# GeigerCounter.net
KiCad netlist of a schematic drawn in EAGLE
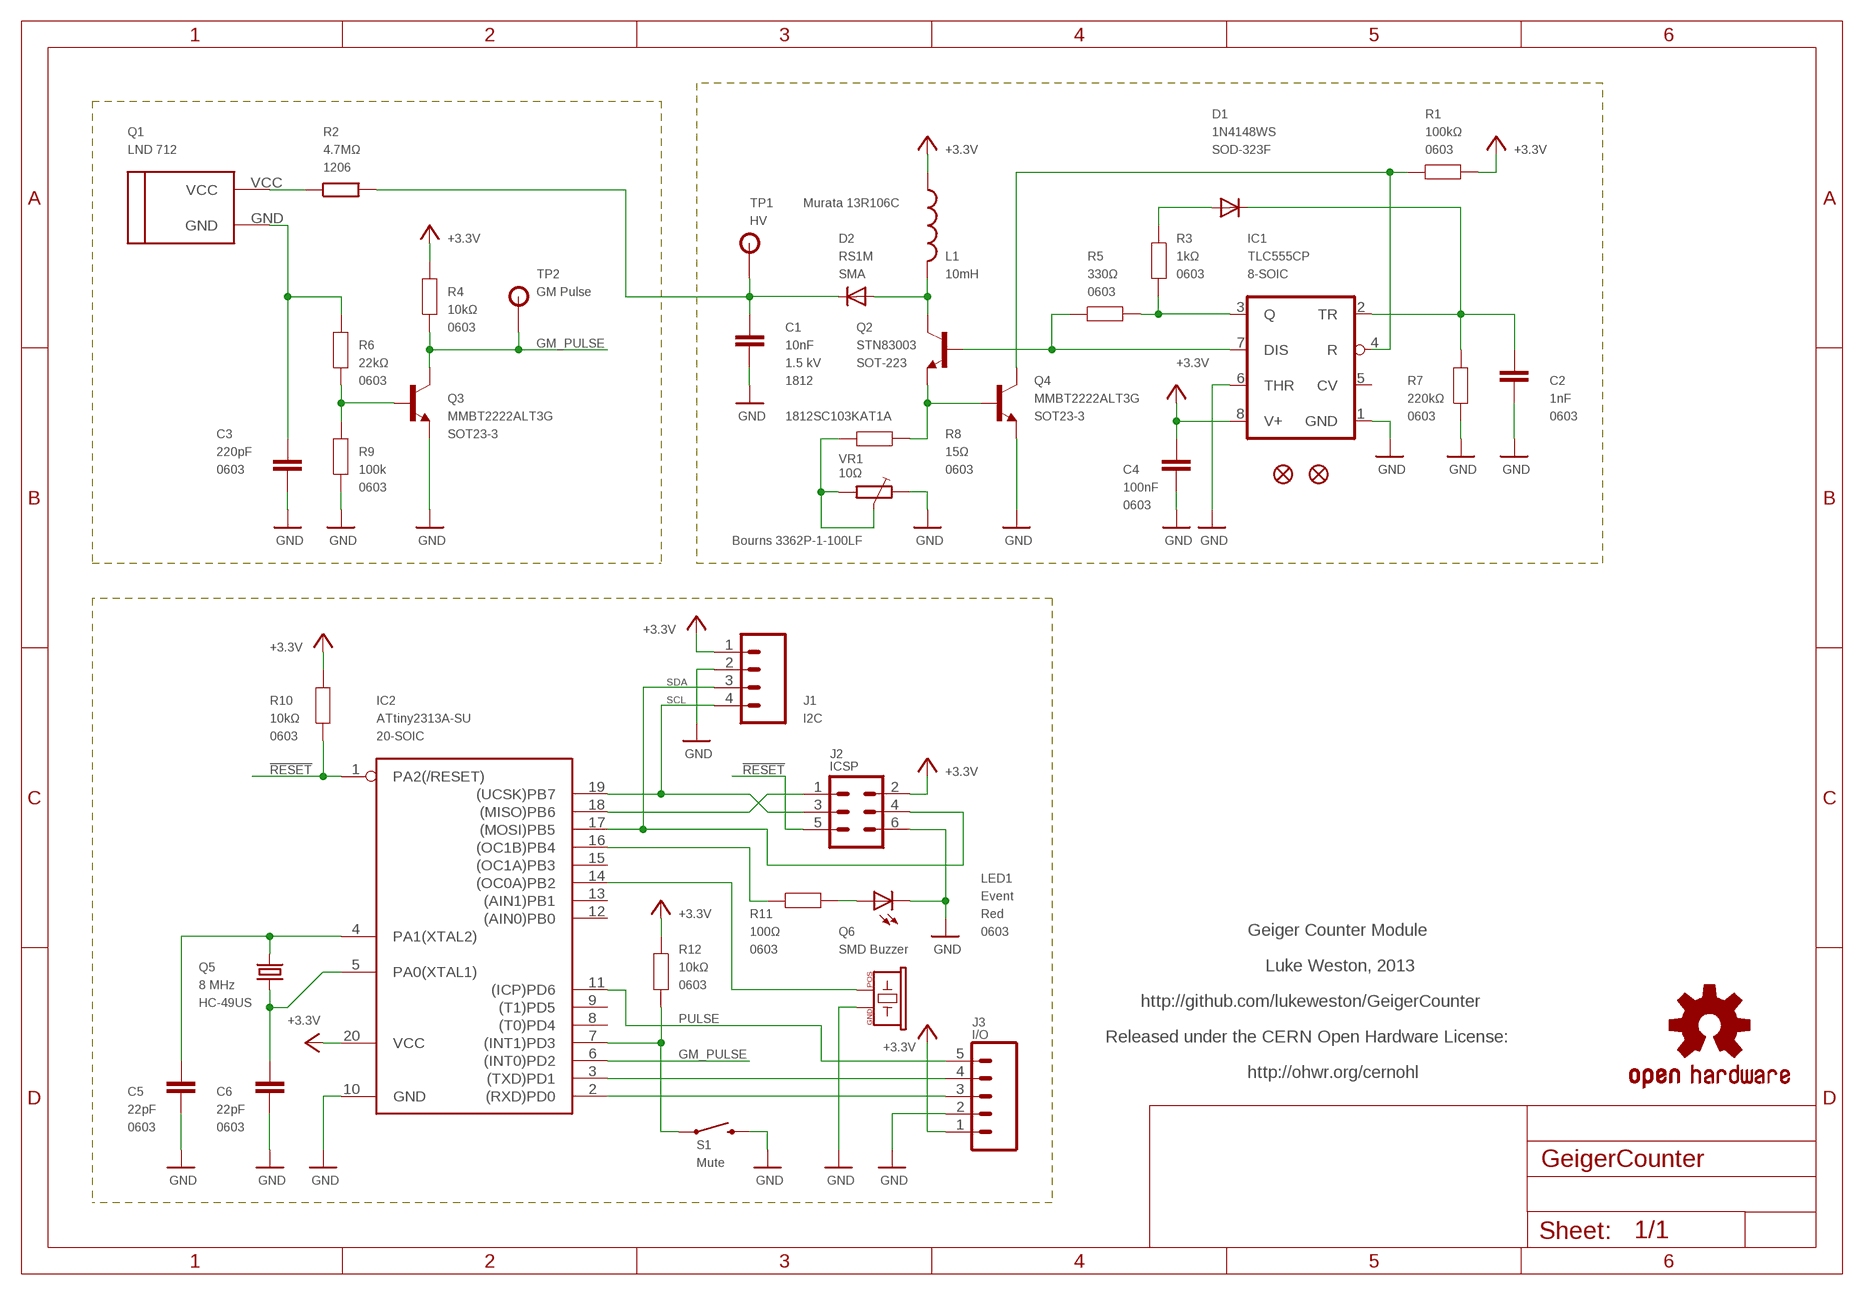
[diagram p0: schematic, sheet 1]

(export (version "E")
  (design (tool "Eeschema 10.0.6"))
  (components
    (comp (ref "C1")
      (value "10nF")
      (footprint "eagle-import:C1812")
      (fields
        (field (name "ID") "1812SC103KAT1A")
        (field (name "PACKAGE") "1812")
        (field (name "VOLTAGE") "1.5 kV")
      )
      (libsource (lib "eagle-import") (part "C-EUC1812"))
    )
    (comp (ref "C2")
      (value "1nF")
      (footprint "eagle-import:0603")
      (fields (field (name "PACKAGE") "0603"))
      (libsource (lib "eagle-import") (part "CAP0603"))
    )
    (comp (ref "C3")
      (value "220pF")
      (footprint "eagle-import:0603")
      (fields (field (name "PACKAGE") "0603"))
      (libsource (lib "eagle-import") (part "CAP0603"))
    )
    (comp (ref "C4")
      (value "100nF")
      (footprint "eagle-import:0603")
      (fields (field (name "PACKAGE") "0603"))
      (libsource (lib "eagle-import") (part "CAP0603"))
    )
    (comp (ref "C5")
      (value "22pF")
      (footprint "eagle-import:0603")
      (fields (field (name "PACKAGE") "0603"))
      (libsource (lib "eagle-import") (part "CAP0603"))
    )
    (comp (ref "C6")
      (value "22pF")
      (footprint "eagle-import:0603")
      (fields (field (name "PACKAGE") "0603"))
      (libsource (lib "eagle-import") (part "CAP0603"))
    )
    (comp (ref "D1")
      (value "1N4148WS")
      (footprint "eagle-import:SOD-323")
      (fields (field (name "PACKAGE") "SOD-323F"))
      (libsource (lib "eagle-import") (part "DIODESOD"))
    )
    (comp (ref "D2")
      (value "RS1M")
      (footprint "eagle-import:DO214AC")
      (fields (field (name "PACKAGE") "SMA"))
      (libsource (lib "eagle-import") (part "DIODE-DO214AC"))
    )
    (comp (ref "IC1")
      (value "TLC555CP")
      (footprint "eagle-import:SO08")
      (fields (field (name "PACKAGE") "8-SOIC"))
      (libsource (lib "eagle-import") (part "555DLM"))
    )
    (comp (ref "IC2")
      (value "ATtiny2313A-SU")
      (footprint "eagle-import:SO20L$")
      (fields (field (name "PACKAGE") "20-SOIC"))
      (libsource (lib "eagle-import") (part "TINY2313-S"))
    )
    (comp (ref "J1")
      (value "I2C")
      (footprint "eagle-import:1X04")
      (libsource (lib "eagle-import") (part "M04PTH"))
    )
    (comp (ref "J2")
      (value "ICSP")
      (footprint "eagle-import:ICSP-6")
      (libsource (lib "eagle-import") (part "ICSP-6"))
    )
    (comp (ref "J3")
      (value "I/O")
      (footprint "eagle-import:1X05")
      (libsource (lib "eagle-import") (part "M05PTH"))
    )
    (comp (ref "JP1")
      (value "FIDUCIALUFIDUCIAL")
      (footprint "eagle-import:MICRO-FIDUCIAL")
      (libsource (lib "eagle-import") (part "FIDUCIALUFIDUCIAL"))
    )
    (comp (ref "JP2")
      (value "FIDUCIALUFIDUCIAL")
      (footprint "eagle-import:MICRO-FIDUCIAL")
      (libsource (lib "eagle-import") (part "FIDUCIALUFIDUCIAL"))
    )
    (comp (ref "L1")
      (value "10mH")
      (footprint "eagle-import:INDUCTOR-5.08")
      (fields (field (name "ID") "Murata 13R106C"))
      (libsource (lib "eagle-import") (part "INDUCTOR-5.08"))
    )
    (comp (ref "LED1")
      (value "Event")
      (footprint "eagle-import:LED-0603")
      (fields (field (name "COLOR") "Red") (field (name "PACKAGE") "0603"))
      (libsource (lib "eagle-import") (part "LED0603"))
    )
    (comp (ref "Q1")
      (value "LND 712")
      (footprint "eagle-import:GEIGER_TUBE")
      (libsource (lib "eagle-import") (part "GEIGER_TUBELND712"))
    )
    (comp (ref "Q2")
      (value "STN83003")
      (footprint "eagle-import:SOT223")
      (fields (field (name "PACKAGE") "SOT-223"))
      (libsource (lib "eagle-import") (part "-NPN-SOT223"))
    )
    (comp (ref "Q3")
      (value "MMBT2222ALT3G")
      (footprint "eagle-import:SOT23")
      (fields (field (name "PACKAGE") "SOT23-3"))
      (libsource (lib "eagle-import") (part "TRANSISTOR_NPNSOT23"))
    )
    (comp (ref "Q4")
      (value "MMBT2222ALT3G")
      (footprint "eagle-import:SOT23")
      (fields (field (name "PACKAGE") "SOT23-3"))
      (libsource (lib "eagle-import") (part "TRANSISTOR_NPNSOT23"))
    )
    (comp (ref "Q5")
      (value "8 MHz")
      (footprint "eagle-import:HC49US")
      (fields (field (name "PACKAGE") "HC-49US"))
      (libsource (lib "eagle-import") (part "CRYSTALHC49US"))
    )
    (comp (ref "Q6")
      (value "SMD Buzzer")
      (footprint "eagle-import:BUZZER-12X12-SMT")
      (libsource (lib "eagle-import") (part "BUZZERSMD12X12"))
    )
    (comp (ref "R1")
      (value "100kΩ")
      (footprint "eagle-import:0603")
      (fields (field (name "PACKAGE") "0603"))
      (libsource (lib "eagle-import") (part "RESISTOR0603"))
    )
    (comp (ref "R2")
      (value "4.7MΩ")
      (footprint "eagle-import:R1206")
      (fields (field (name "PACKAGE") "1206"))
      (libsource (lib "eagle-import") (part "R-EU_R1206"))
    )
    (comp (ref "R3")
      (value "1kΩ")
      (footprint "eagle-import:0603")
      (fields (field (name "PACKAGE") "0603"))
      (libsource (lib "eagle-import") (part "RESISTOR0603"))
    )
    (comp (ref "R4")
      (value "10kΩ")
      (footprint "eagle-import:0603")
      (fields (field (name "PACKAGE") "0603"))
      (libsource (lib "eagle-import") (part "RESISTOR0603"))
    )
    (comp (ref "R5")
      (value "330Ω")
      (footprint "eagle-import:0603")
      (fields (field (name "PACKAGE") "0603"))
      (libsource (lib "eagle-import") (part "RESISTOR0603"))
    )
    (comp (ref "R6")
      (value "22kΩ")
      (footprint "eagle-import:0603")
      (fields (field (name "PACKAGE") "0603"))
      (libsource (lib "eagle-import") (part "RESISTOR0603"))
    )
    (comp (ref "R7")
      (value "220kΩ")
      (footprint "eagle-import:0603")
      (fields (field (name "PACKAGE") "0603"))
      (libsource (lib "eagle-import") (part "RESISTOR0603"))
    )
    (comp (ref "R8")
      (value "15Ω")
      (footprint "eagle-import:0603")
      (fields (field (name "PACKAGE") "0603"))
      (libsource (lib "eagle-import") (part "RESISTOR0603"))
    )
    (comp (ref "R9")
      (value "100k")
      (footprint "eagle-import:0603")
      (fields (field (name "PACKAGE") "0603"))
      (libsource (lib "eagle-import") (part "RESISTOR0603"))
    )
    (comp (ref "R10")
      (value "10kΩ")
      (footprint "eagle-import:0603")
      (fields (field (name "PACKAGE") "0603"))
      (libsource (lib "eagle-import") (part "RESISTOR0603"))
    )
    (comp (ref "R11")
      (value "100Ω")
      (footprint "eagle-import:0603")
      (fields (field (name "PACKAGE") "0603"))
      (libsource (lib "eagle-import") (part "RESISTOR0603"))
    )
    (comp (ref "R12")
      (value "10kΩ")
      (footprint "eagle-import:0603")
      (fields (field (name "PACKAGE") "0603"))
      (libsource (lib "eagle-import") (part "RESISTOR0603"))
    )
    (comp (ref "S1")
      (value "Mute")
      (footprint "eagle-import:TACTILE_SWITCH_SMD")
      (libsource (lib "eagle-import") (part "SWITCH-MOMENTARY-2SMD"))
    )
    (comp (ref "SY")
      (value "OSHW-LOGOS")
      (footprint "eagle-import:OSHW-LOGO-S")
      (libsource (lib "eagle-import") (part "OSHW-LOGOS"))
    )
    (comp (ref "TP1")
      (value "HV")
      (footprint "eagle-import:TP_PTH")
      (libsource (lib "eagle-import") (part "TPPTH"))
    )
    (comp (ref "TP2")
      (value "GM Pulse")
      (footprint "eagle-import:TP_PTH")
      (libsource (lib "eagle-import") (part "TPPTH"))
    )
    (comp (ref "VR1")
      (value "10Ω")
      (footprint "eagle-import:CT6")
      (fields (field (name "ID") "Bourns 3362P-1-100LF"))
      (libsource (lib "eagle-import") (part "TRIM_EU-CT6"))
    )
  )
  (nets
    (net (code "1") (name "+3.3V") (class "Default")
      (node (ref "C4") (pin "1") (pinfunction "1_1") (pintype "passive"))
      (node (ref "IC1") (pin "8") (pinfunction "V+_8") (pintype "power_in"))
      (node (ref "IC2") (pin "20") (pinfunction "VCC_20") (pintype "power_in"))
      (node (ref "J1") (pin "1") (pinfunction "1_1") (pintype "passive"))
      (node (ref "J2") (pin "2") (pinfunction "2_2") (pintype "passive"))
      (node (ref "J3") (pin "1") (pinfunction "1_1") (pintype "passive"))
      (node (ref "L1") (pin "1") (pinfunction "1_1") (pintype "passive"))
      (node (ref "R1") (pin "1") (pinfunction "1_1") (pintype "passive"))
      (node (ref "R10") (pin "2") (pinfunction "2_2") (pintype "passive"))
      (node (ref "R12") (pin "1") (pinfunction "1_1") (pintype "passive"))
      (node (ref "R4") (pin "2") (pinfunction "2_2") (pintype "passive"))
    )
    (net (code "2") (name "/GM_PULSE") (class "Default")
      (node (ref "IC2") (pin "6") (pinfunction "(INT0)PD2_6") (pintype "bidirectional"))
      (node (ref "Q3") (pin "3") (pinfunction "C_3") (pintype "passive"))
      (node (ref "R4") (pin "1") (pinfunction "1_1") (pintype "passive"))
      (node (ref "TP2") (pin "P$1") (pinfunction "TP_P$1") (pintype "bidirectional"))
    )
    (net (code "3") (name "/PULSE") (class "Default")
      (node (ref "IC2") (pin "11") (pinfunction "(ICP)PD6_11") (pintype "bidirectional"))
      (node (ref "J3") (pin "5") (pinfunction "5_5") (pintype "passive"))
    )
    (net (code "4") (name "/SCL") (class "Default")
      (node (ref "IC2") (pin "19") (pinfunction "(UCSK)PB7_19") (pintype "bidirectional"))
      (node (ref "J1") (pin "4") (pinfunction "4_4") (pintype "passive"))
      (node (ref "J2") (pin "3") (pinfunction "3_3") (pintype "passive"))
    )
    (net (code "5") (name "/SDA") (class "Default")
      (node (ref "IC2") (pin "17") (pinfunction "(MOSI)PB5_17") (pintype "bidirectional"))
      (node (ref "J1") (pin "3") (pinfunction "3_3") (pintype "passive"))
      (node (ref "J2") (pin "4") (pinfunction "4_4") (pintype "passive"))
    )
    (net (code "6") (name "/~{RESET}") (class "Default")
      (node (ref "IC2") (pin "1") (pinfunction "PA2(/RESET)_1") (pintype "input"))
      (node (ref "J2") (pin "5") (pinfunction "5_5") (pintype "passive"))
      (node (ref "R10") (pin "1") (pinfunction "1_1") (pintype "passive"))
    )
    (net (code "7") (name "GND") (class "Default")
      (node (ref "C1") (pin "2") (pinfunction "2_2") (pintype "passive"))
      (node (ref "C2") (pin "2") (pinfunction "2_2") (pintype "passive"))
      (node (ref "C3") (pin "2") (pinfunction "2_2") (pintype "passive"))
      (node (ref "C4") (pin "2") (pinfunction "2_2") (pintype "passive"))
      (node (ref "C5") (pin "2") (pinfunction "2_2") (pintype "passive"))
      (node (ref "C6") (pin "2") (pinfunction "2_2") (pintype "passive"))
      (node (ref "IC1") (pin "1") (pinfunction "GND_1") (pintype "power_in"))
      (node (ref "IC1") (pin "6") (pinfunction "THR_6") (pintype "input"))
      (node (ref "IC2") (pin "10") (pinfunction "GND_10") (pintype "power_in"))
      (node (ref "J1") (pin "2") (pinfunction "2_2") (pintype "passive"))
      (node (ref "J2") (pin "6") (pinfunction "6_6") (pintype "passive"))
      (node (ref "J3") (pin "2") (pinfunction "2_2") (pintype "passive"))
      (node (ref "LED1") (pin "C") (pinfunction "C_C") (pintype "passive"))
      (node (ref "Q3") (pin "2") (pinfunction "E_2") (pintype "passive"))
      (node (ref "Q4") (pin "2") (pinfunction "E_2") (pintype "passive"))
      (node (ref "Q6") (pin "1") (pinfunction "GND_1") (pintype "passive"))
      (node (ref "R7") (pin "1") (pinfunction "1_1") (pintype "passive"))
      (node (ref "R9") (pin "1") (pinfunction "1_1") (pintype "passive"))
      (node (ref "S1") (pin "3") (pinfunction "2_3") (pintype "passive"))
      (node (ref "VR1") (pin "E") (pinfunction "E_E") (pintype "passive"))
    )
    (net (code "8") (name "Net-(C3-Pad1)") (class "Default")
      (node (ref "C3") (pin "1") (pinfunction "1_1") (pintype "passive"))
      (node (ref "Q1") (pin "GND") (pinfunction "GND_GND") (pintype "bidirectional"))
      (node (ref "R6") (pin "2") (pinfunction "2_2") (pintype "passive"))
    )
    (net (code "9") (name "Net-(D1-A)") (class "Default")
      (node (ref "D1") (pin "2") (pinfunction "A_2") (pintype "passive"))
      (node (ref "R3") (pin "1") (pinfunction "1_1") (pintype "passive"))
    )
    (net (code "10") (name "Net-(D1-C)") (class "Default")
      (node (ref "C2") (pin "1") (pinfunction "1_1") (pintype "passive"))
      (node (ref "D1") (pin "1") (pinfunction "C_1") (pintype "passive"))
      (node (ref "IC1") (pin "2") (pinfunction "TR_2") (pintype "input"))
      (node (ref "R7") (pin "2") (pinfunction "2_2") (pintype "passive"))
    )
    (net (code "11") (name "Net-(IC1-DIS)") (class "Default")
      (node (ref "IC1") (pin "7") (pinfunction "DIS_7") (pintype "input"))
      (node (ref "Q2") (pin "1") (pinfunction "B_1") (pintype "passive"))
      (node (ref "R5") (pin "2") (pinfunction "2_2") (pintype "passive"))
    )
    (net (code "12") (name "Net-(IC1-Q)") (class "Default")
      (node (ref "IC1") (pin "3") (pinfunction "Q_3") (pintype "output"))
      (node (ref "R3") (pin "2") (pinfunction "2_2") (pintype "passive"))
      (node (ref "R5") (pin "1") (pinfunction "1_1") (pintype "passive"))
    )
    (net (code "13") (name "Net-(IC1-R)") (class "Default")
      (node (ref "IC1") (pin "4") (pinfunction "R_4") (pintype "input"))
      (node (ref "Q4") (pin "3") (pinfunction "C_3") (pintype "passive"))
      (node (ref "R1") (pin "2") (pinfunction "2_2") (pintype "passive"))
    )
    (net (code "14") (name "Net-(IC2-(INT1)PD3)") (class "Default")
      (node (ref "IC2") (pin "7") (pinfunction "(INT1)PD3_7") (pintype "bidirectional"))
      (node (ref "R12") (pin "2") (pinfunction "2_2") (pintype "passive"))
      (node (ref "S1") (pin "1") (pinfunction "1_1") (pintype "passive"))
    )
    (net (code "15") (name "Net-(IC2-(MISO)PB6)") (class "Default")
      (node (ref "IC2") (pin "18") (pinfunction "(MISO)PB6_18") (pintype "bidirectional"))
      (node (ref "J2") (pin "1") (pinfunction "1_1") (pintype "passive"))
    )
    (net (code "16") (name "Net-(IC2-(OC0A)PB2)") (class "Default")
      (node (ref "IC2") (pin "14") (pinfunction "(OC0A)PB2_14") (pintype "bidirectional"))
      (node (ref "Q6") (pin "2") (pinfunction "POS_2") (pintype "passive"))
    )
    (net (code "17") (name "Net-(IC2-(OC1B)PB4)") (class "Default")
      (node (ref "IC2") (pin "16") (pinfunction "(OC1B)PB4_16") (pintype "bidirectional"))
      (node (ref "R11") (pin "2") (pinfunction "2_2") (pintype "passive"))
    )
    (net (code "18") (name "Net-(IC2-(RXD)PD0)") (class "Default")
      (node (ref "IC2") (pin "2") (pinfunction "(RXD)PD0_2") (pintype "bidirectional"))
      (node (ref "J3") (pin "3") (pinfunction "3_3") (pintype "passive"))
    )
    (net (code "19") (name "Net-(IC2-(TXD)PD1)") (class "Default")
      (node (ref "IC2") (pin "3") (pinfunction "(TXD)PD1_3") (pintype "bidirectional"))
      (node (ref "J3") (pin "4") (pinfunction "4_4") (pintype "passive"))
    )
    (net (code "20") (name "Net-(IC2-PA0(XTAL1))") (class "Default")
      (node (ref "C6") (pin "1") (pinfunction "1_1") (pintype "passive"))
      (node (ref "IC2") (pin "5") (pinfunction "PA0(XTAL1)_5") (pintype "bidirectional"))
      (node (ref "Q5") (pin "1") (pinfunction "1_1") (pintype "passive"))
    )
    (net (code "21") (name "Net-(IC2-PA1(XTAL2))") (class "Default")
      (node (ref "C5") (pin "1") (pinfunction "1_1") (pintype "passive"))
      (node (ref "IC2") (pin "4") (pinfunction "PA1(XTAL2)_4") (pintype "bidirectional"))
      (node (ref "Q5") (pin "2") (pinfunction "2_2") (pintype "passive"))
    )
    (net (code "22") (name "Net-(LED1-PadA)") (class "Default")
      (node (ref "LED1") (pin "A") (pinfunction "A_A") (pintype "passive"))
      (node (ref "R11") (pin "1") (pinfunction "1_1") (pintype "passive"))
    )
    (net (code "23") (name "Net-(Q1-PadVCC)") (class "Default")
      (node (ref "Q1") (pin "VCC") (pinfunction "VCC_VCC") (pintype "bidirectional"))
      (node (ref "R2") (pin "1") (pinfunction "1_1") (pintype "passive"))
    )
    (net (code "24") (name "Net-(Q2-C)") (class "Default")
      (node (ref "D2") (pin "A") (pinfunction "A_A") (pintype "passive"))
      (node (ref "L1") (pin "2") (pinfunction "2_2") (pintype "passive"))
      (node (ref "Q2") (pin "4") (pinfunction "C_4") (pintype "passive"))
    )
    (net (code "25") (name "Net-(Q2-E)") (class "Default")
      (node (ref "Q2") (pin "3") (pinfunction "E_3") (pintype "passive"))
      (node (ref "Q4") (pin "1") (pinfunction "B_1") (pintype "passive"))
      (node (ref "R8") (pin "2") (pinfunction "2_2") (pintype "passive"))
    )
    (net (code "26") (name "Net-(Q3-B)") (class "Default")
      (node (ref "Q3") (pin "1") (pinfunction "B_1") (pintype "passive"))
      (node (ref "R6") (pin "1") (pinfunction "1_1") (pintype "passive"))
      (node (ref "R9") (pin "2") (pinfunction "2_2") (pintype "passive"))
    )
    (net (code "27") (name "Net-(R8-Pad1)") (class "Default")
      (node (ref "R8") (pin "1") (pinfunction "1_1") (pintype "passive"))
      (node (ref "VR1") (pin "A") (pinfunction "A_A") (pintype "passive"))
      (node (ref "VR1") (pin "S") (pinfunction "S_S") (pintype "passive"))
    )
    (net (code "28") (name "Net-(TP1-TP)") (class "Default")
      (node (ref "C1") (pin "1") (pinfunction "1_1") (pintype "passive"))
      (node (ref "D2") (pin "C") (pinfunction "C_C") (pintype "passive"))
      (node (ref "R2") (pin "2") (pinfunction "2_2") (pintype "passive"))
      (node (ref "TP1") (pin "P$1") (pinfunction "TP_P$1") (pintype "bidirectional"))
    )
    (net (code "29") (name "unconnected-(IC1-CV-Pad5)") (class "Default")
      (node (ref "IC1") (pin "5") (pinfunction "CV_5") (pintype "input"))
    )
    (net (code "30") (name "unconnected-(IC2-(AIN0)PB0-Pad12)") (class "Default")
      (node (ref "IC2") (pin "12") (pinfunction "(AIN0)PB0_12") (pintype "bidirectional"))
    )
    (net (code "31") (name "unconnected-(IC2-(AIN1)PB1-Pad13)") (class "Default")
      (node (ref "IC2") (pin "13") (pinfunction "(AIN1)PB1_13") (pintype "bidirectional"))
    )
    (net (code "32") (name "unconnected-(IC2-(OC1A)PB3-Pad15)") (class "Default")
      (node (ref "IC2") (pin "15") (pinfunction "(OC1A)PB3_15") (pintype "bidirectional"))
    )
    (net (code "33") (name "unconnected-(IC2-(T0)PD4-Pad8)") (class "Default")
      (node (ref "IC2") (pin "8") (pinfunction "(T0)PD4_8") (pintype "bidirectional"))
    )
    (net (code "34") (name "unconnected-(IC2-(T1)PD5-Pad9)") (class "Default")
      (node (ref "IC2") (pin "9") (pinfunction "(T1)PD5_9") (pintype "bidirectional"))
    )
  )
)
